# peripherals.net
KiCad netlist of a schematic drawn in Altium Designer
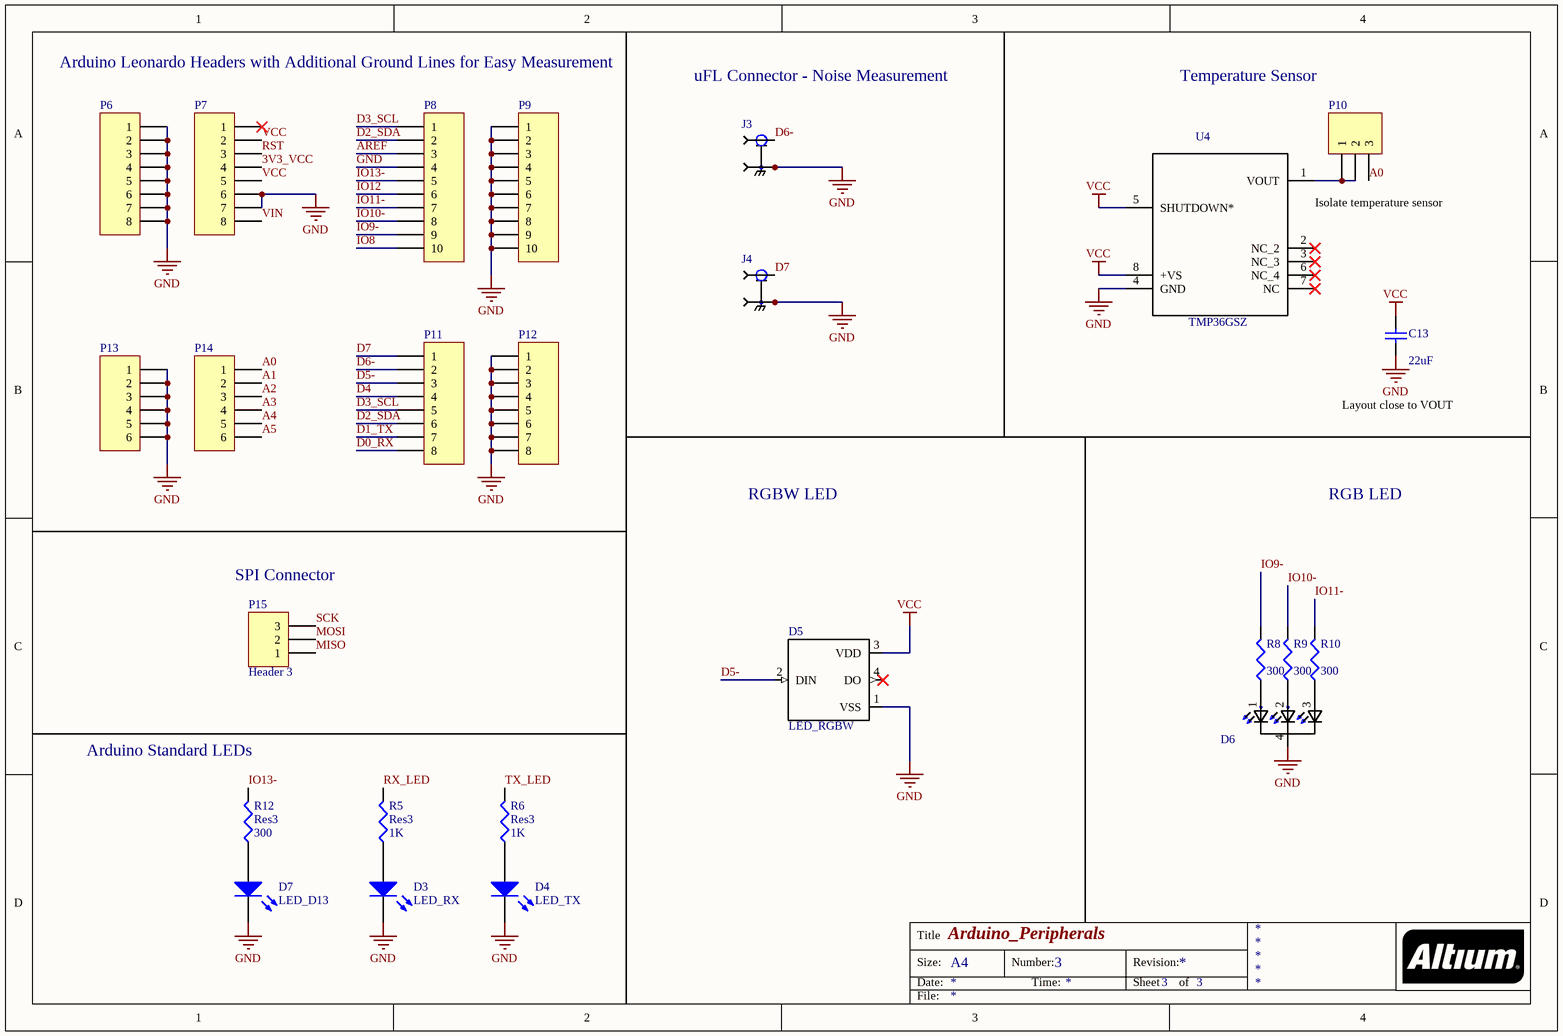
[diagram p0: peripherals.SchDoc]

(export (version "E")
  (design (tool "Eeschema 10.0.6"))
  (components
    (comp (ref "C13")
      (value "22uF")
      (footprint "C1206")
      (description "Capacitor (Semiconductor SIM Model)")
      (fields
        (field (name "DIGIKEYPARTNO") "1276-3300-1-ND")
        (field (name "Comment") "Cap Semi")
        (field (name "PUBLISHER") "Altium Limited")
      )
      (libsource (lib "Miscellaneous Devices") (part "Cap Semi"))
    )
    (comp (ref "D3")
      (value "LED_RX")
      (footprint "3.2X1.6X1.1")
      (description "Typical RED, GREEN, YELLOW, AMBER GaAs LED")
      (fields (field (name "PUBLISHER") "Altium Limited"))
      (libsource (lib "Miscellaneous Devices") (part "LED2"))
    )
    (comp (ref "D4")
      (value "LED_TX")
      (footprint "3.2X1.6X1.1")
      (description "Typical RED, GREEN, YELLOW, AMBER GaAs LED")
      (fields (field (name "PUBLISHER") "Altium Limited"))
      (libsource (lib "Miscellaneous Devices") (part "LED2"))
    )
    (comp (ref "D5")
      (value "LED_RGBW")
      (footprint "*LED_IN-PI554FCH")
      (description "5050RGB with integrated IC built in 4 PIN Â•Viewing angle: 120 degrees")
      (fields (field (name "MP") "IN-PI554FCH") (field (name "MF") "Inolux"))
      (libsource (lib "IN-PI554FCH") (part "IN-PI554FCH"))
    )
    (comp (ref "D6")
      (value "LED_RGB")
      (footprint "*LED_ASMB-KTF0-0A306")
      (description "2220 Tricolor PLCC4 Surface Mount LED")
      (fields (field (name "MP") "XZM2CRKM2DGFBB45SCCB") (field (name "MF") "SunLED"))
      (libsource (lib "ASMB-KTF0-0A306") (part "ASMB-KTF0-0A306"))
    )
    (comp (ref "D7")
      (value "LED_D13")
      (footprint "3.2X1.6X1.1")
      (description "Typical RED, GREEN, YELLOW, AMBER GaAs LED")
      (fields (field (name "PUBLISHER") "Altium Limited"))
      (libsource (lib "Miscellaneous Devices") (part "LED2"))
    )
    (comp (ref "J3")
      (value "U.FL-R-SMT(10)")
      (footprint "*TE_HRS_U.FL-R-SMT(10)")
      (description "U.FL Series 50 Ohm Receptacle Male Pins Ultra Small SMT Coaxial Connector")
      (fields (field (name "MF") "Hirose") (field (name "MP") "U.FL-R-SMT_10_"))
      (libsource (lib "U.FL-R-SMT_10_") (part "U.FL-R-SMT(10)"))
    )
    (comp (ref "J4")
      (value "U.FL-R-SMT(10)")
      (footprint "*TE_HRS_U.FL-R-SMT(10)")
      (description "U.FL Series 50 Ohm Receptacle Male Pins Ultra Small SMT Coaxial Connector")
      (fields (field (name "MF") "Hirose") (field (name "MP") "U.FL-R-SMT_10_"))
      (libsource (lib "U.FL-R-SMT_10_") (part "U.FL-R-SMT(10)"))
    )
    (comp (ref "P6")
      (value "GND")
      (footprint "HDR1X8")
      (description "Header, 8-Pin")
      (fields (field (name "PUBLISHER") "Altium Limited"))
      (libsource (lib "Miscellaneous Connectors") (part "Header 8"))
    )
    (comp (ref "P7")
      (value "P4")
      (footprint "HDR1X8")
      (description "Header, 8-Pin")
      (fields (field (name "PUBLISHER") "Altium Limited"))
      (libsource (lib "Miscellaneous Connectors") (part "Header 8"))
    )
    (comp (ref "P8")
      (value "P1")
      (footprint "HDR1X10")
      (description "Header, 10-Pin")
      (fields (field (name "PUBLISHER") "Altium Limited"))
      (libsource (lib "Miscellaneous Connectors") (part "Header 10"))
    )
    (comp (ref "P9")
      (value "GND")
      (footprint "HDR1X10")
      (description "Header, 10-Pin")
      (fields (field (name "PUBLISHER") "Altium Limited"))
      (libsource (lib "Miscellaneous Connectors") (part "Header 10"))
    )
    (comp (ref "P10")
      (value "NC A0")
      (footprint "HDR1X3")
      (description "Header, 3-Pin")
      (fields (field (name "PUBLISHER") "Altium Limited"))
      (libsource (lib "Miscellaneous Connectors") (part "Header 3"))
    )
    (comp (ref "P11")
      (value "P2")
      (footprint "HDR1X8")
      (description "Header, 8-Pin")
      (fields (field (name "PUBLISHER") "Altium Limited"))
      (libsource (lib "") (part "Header 8_1"))
    )
    (comp (ref "P12")
      (value "GND")
      (footprint "HDR1X8")
      (description "Header, 8-Pin")
      (fields (field (name "PUBLISHER") "Altium Limited"))
      (libsource (lib "") (part "Header 8_1"))
    )
    (comp (ref "P13")
      (value "GND")
      (footprint "HDR1X6")
      (description "Header, 6-Pin")
      (fields (field (name "PUBLISHER") "Altium Limited"))
      (libsource (lib "Miscellaneous Connectors") (part "Header 6"))
    )
    (comp (ref "P14")
      (value "P3")
      (footprint "HDR1X6")
      (description "Header, 6-Pin")
      (fields (field (name "PUBLISHER") "Altium Limited"))
      (libsource (lib "Miscellaneous Connectors") (part "Header 6"))
    )
    (comp (ref "P15")
      (value "Header 3")
      (footprint "HDR1X3")
      (description "Header, 3-Pin")
      (fields (field (name "PUBLISHER") "Altium Limited"))
      (libsource (lib "") (part "Header 3_1"))
    )
    (comp (ref "R5")
      (value "Res3")
      (footprint "C1206")
      (description "Resistor")
      (fields (field (name "ALTIUM_VALUE") "1K") (field (name "PUBLISHER") "Altium Limited"))
      (libsource (lib "Miscellaneous Devices") (part "Res3"))
    )
    (comp (ref "R6")
      (value "Res3")
      (footprint "C1206")
      (description "Resistor")
      (fields (field (name "ALTIUM_VALUE") "1K") (field (name "PUBLISHER") "Altium Limited"))
      (libsource (lib "Miscellaneous Devices") (part "Res3"))
    )
    (comp (ref "R8")
      (value "300")
      (footprint "C1206")
      (description "Resistor")
      (fields (field (name "Comment") "Res3") (field (name "PUBLISHER") "Altium Limited"))
      (libsource (lib "Miscellaneous Devices") (part "Res3"))
    )
    (comp (ref "R9")
      (value "300")
      (footprint "C1206")
      (description "Resistor")
      (fields (field (name "Comment") "Res3") (field (name "PUBLISHER") "Altium Limited"))
      (libsource (lib "Miscellaneous Devices") (part "Res3"))
    )
    (comp (ref "R10")
      (value "300")
      (footprint "C1206")
      (description "Resistor")
      (fields (field (name "Comment") "Res3") (field (name "PUBLISHER") "Altium Limited"))
      (libsource (lib "Miscellaneous Devices") (part "Res3"))
    )
    (comp (ref "R12")
      (value "Res3")
      (footprint "C1206")
      (description "Resistor")
      (fields (field (name "ALTIUM_VALUE") "300") (field (name "PUBLISHER") "Altium Limited"))
      (libsource (lib "Miscellaneous Devices") (part "Res3"))
    )
    (comp (ref "U4")
      (value "TMP36GSZ")
      (footprint "*SOIC127P600X175-8N")
      (description "Temp Sensor Analog_Voltage_ Serial _2-Wire_ 8-Pin SOIC N Tube")
      (fields (field (name "MF") "Analog Devices"))
      (libsource (lib "TMP36GSZ") (part "TMP36GSZ"))
    )
  )
  (nets
    (net (code "1") (name "/3V3_VCC") (class "Default")
      (node (ref "P7") (pin "4") (pinfunction "4_4") (pintype "passive"))
    )
    (net (code "2") (name "/A0") (class "Default")
      (node (ref "P10") (pin "3") (pinfunction "3_3") (pintype "passive"))
      (node (ref "P14") (pin "1") (pinfunction "1_1") (pintype "passive"))
    )
    (net (code "3") (name "/A1") (class "Default")
      (node (ref "P14") (pin "2") (pinfunction "2_2") (pintype "passive"))
    )
    (net (code "4") (name "/A2") (class "Default")
      (node (ref "P14") (pin "3") (pinfunction "3_3") (pintype "passive"))
    )
    (net (code "5") (name "/A3") (class "Default")
      (node (ref "P14") (pin "4") (pinfunction "4_4") (pintype "passive"))
    )
    (net (code "6") (name "/A4") (class "Default")
      (node (ref "P14") (pin "5") (pinfunction "5_5") (pintype "passive"))
    )
    (net (code "7") (name "/A5") (class "Default")
      (node (ref "P14") (pin "6") (pinfunction "6_6") (pintype "passive"))
    )
    (net (code "8") (name "/AREF") (class "Default")
      (node (ref "P8") (pin "3") (pinfunction "3_3") (pintype "passive"))
    )
    (net (code "9") (name "/D0_RX") (class "Default")
      (node (ref "P11") (pin "8") (pinfunction "8_8") (pintype "passive"))
    )
    (net (code "10") (name "/D1_TX") (class "Default")
      (node (ref "P11") (pin "7") (pinfunction "7_7") (pintype "passive"))
    )
    (net (code "11") (name "/D2_SDA") (class "Default")
      (node (ref "P11") (pin "6") (pinfunction "6_6") (pintype "passive"))
      (node (ref "P8") (pin "2") (pinfunction "2_2") (pintype "passive"))
    )
    (net (code "12") (name "/D3_SCL") (class "Default")
      (node (ref "P11") (pin "5") (pinfunction "5_5") (pintype "passive"))
      (node (ref "P8") (pin "1") (pinfunction "1_1") (pintype "passive"))
    )
    (net (code "13") (name "/D4") (class "Default")
      (node (ref "P11") (pin "4") (pinfunction "4_4") (pintype "passive"))
    )
    (net (code "14") (name "/D5-") (class "Default")
      (node (ref "D5") (pin "2") (pinfunction "DIN_2") (pintype "input"))
      (node (ref "P11") (pin "3") (pinfunction "3_3") (pintype "passive"))
    )
    (net (code "15") (name "/D6-") (class "Default")
      (node (ref "J3") (pin "1") (pinfunction "SIG_1") (pintype "passive"))
      (node (ref "P11") (pin "2") (pinfunction "2_2") (pintype "passive"))
    )
    (net (code "16") (name "/D7") (class "Default")
      (node (ref "J4") (pin "1") (pinfunction "SIG_1") (pintype "passive"))
      (node (ref "P11") (pin "1") (pinfunction "1_1") (pintype "passive"))
    )
    (net (code "17") (name "/IO8") (class "Default")
      (node (ref "P8") (pin "10") (pinfunction "10_10") (pintype "passive"))
    )
    (net (code "18") (name "/IO9-") (class "Default")
      (node (ref "P8") (pin "9") (pinfunction "9_9") (pintype "passive"))
      (node (ref "R8") (pin "2") (pinfunction "2_2") (pintype "passive"))
    )
    (net (code "19") (name "/IO10-") (class "Default")
      (node (ref "P8") (pin "8") (pinfunction "8_8") (pintype "passive"))
      (node (ref "R9") (pin "2") (pinfunction "2_2") (pintype "passive"))
    )
    (net (code "20") (name "/IO11-") (class "Default")
      (node (ref "P8") (pin "7") (pinfunction "7_7") (pintype "passive"))
      (node (ref "R10") (pin "2") (pinfunction "2_2") (pintype "passive"))
    )
    (net (code "21") (name "/IO12") (class "Default")
      (node (ref "P8") (pin "6") (pinfunction "6_6") (pintype "passive"))
    )
    (net (code "22") (name "/IO13-") (class "Default")
      (node (ref "P8") (pin "5") (pinfunction "5_5") (pintype "passive"))
      (node (ref "R12") (pin "2") (pinfunction "2_2") (pintype "passive"))
    )
    (net (code "23") (name "/MISO") (class "Default")
      (node (ref "P15") (pin "1") (pinfunction "1_1") (pintype "passive"))
    )
    (net (code "24") (name "/MOSI") (class "Default")
      (node (ref "P15") (pin "2") (pinfunction "2_2") (pintype "passive"))
    )
    (net (code "25") (name "/RST") (class "Default")
      (node (ref "P7") (pin "3") (pinfunction "3_3") (pintype "passive"))
    )
    (net (code "26") (name "/RX_LED") (class "Default")
      (node (ref "R5") (pin "2") (pinfunction "2_2") (pintype "passive"))
    )
    (net (code "27") (name "/SCK") (class "Default")
      (node (ref "P15") (pin "3") (pinfunction "3_3") (pintype "passive"))
    )
    (net (code "28") (name "/TX_LED") (class "Default")
      (node (ref "R6") (pin "2") (pinfunction "2_2") (pintype "passive"))
    )
    (net (code "29") (name "/VIN") (class "Default")
      (node (ref "P7") (pin "8") (pinfunction "8_8") (pintype "passive"))
    )
    (net (code "30") (name "GND") (class "Default")
      (node (ref "C13") (pin "1") (pinfunction "1_1") (pintype "passive"))
      (node (ref "D3") (pin "2") (pinfunction "K_2") (pintype "passive"))
      (node (ref "D4") (pin "2") (pinfunction "K_2") (pintype "passive"))
      (node (ref "D5") (pin "1") (pinfunction "VSS_1") (pintype "power_in"))
      (node (ref "D6") (pin "4") (pinfunction "C_4") (pintype "passive"))
      (node (ref "D7") (pin "2") (pinfunction "K_2") (pintype "passive"))
      (node (ref "J3") (pin "2") (pinfunction "GND_2") (pintype "passive"))
      (node (ref "J3") (pin "3") (pinfunction "GND_3") (pintype "passive"))
      (node (ref "J4") (pin "2") (pinfunction "GND_2") (pintype "passive"))
      (node (ref "J4") (pin "3") (pinfunction "GND_3") (pintype "passive"))
      (node (ref "P12") (pin "1") (pinfunction "1_1") (pintype "passive"))
      (node (ref "P12") (pin "2") (pinfunction "2_2") (pintype "passive"))
      (node (ref "P12") (pin "3") (pinfunction "3_3") (pintype "passive"))
      (node (ref "P12") (pin "4") (pinfunction "4_4") (pintype "passive"))
      (node (ref "P12") (pin "5") (pinfunction "5_5") (pintype "passive"))
      (node (ref "P12") (pin "6") (pinfunction "6_6") (pintype "passive"))
      (node (ref "P12") (pin "7") (pinfunction "7_7") (pintype "passive"))
      (node (ref "P12") (pin "8") (pinfunction "8_8") (pintype "passive"))
      (node (ref "P13") (pin "1") (pinfunction "1_1") (pintype "passive"))
      (node (ref "P13") (pin "2") (pinfunction "2_2") (pintype "passive"))
      (node (ref "P13") (pin "3") (pinfunction "3_3") (pintype "passive"))
      (node (ref "P13") (pin "4") (pinfunction "4_4") (pintype "passive"))
      (node (ref "P13") (pin "5") (pinfunction "5_5") (pintype "passive"))
      (node (ref "P13") (pin "6") (pinfunction "6_6") (pintype "passive"))
      (node (ref "P6") (pin "1") (pinfunction "1_1") (pintype "passive"))
      (node (ref "P6") (pin "2") (pinfunction "2_2") (pintype "passive"))
      (node (ref "P6") (pin "3") (pinfunction "3_3") (pintype "passive"))
      (node (ref "P6") (pin "4") (pinfunction "4_4") (pintype "passive"))
      (node (ref "P6") (pin "5") (pinfunction "5_5") (pintype "passive"))
      (node (ref "P6") (pin "6") (pinfunction "6_6") (pintype "passive"))
      (node (ref "P6") (pin "7") (pinfunction "7_7") (pintype "passive"))
      (node (ref "P6") (pin "8") (pinfunction "8_8") (pintype "passive"))
      (node (ref "P7") (pin "6") (pinfunction "6_6") (pintype "passive"))
      (node (ref "P7") (pin "7") (pinfunction "7_7") (pintype "passive"))
      (node (ref "P8") (pin "4") (pinfunction "4_4") (pintype "passive"))
      (node (ref "P9") (pin "1") (pinfunction "1_1") (pintype "passive"))
      (node (ref "P9") (pin "10") (pinfunction "10_10") (pintype "passive"))
      (node (ref "P9") (pin "2") (pinfunction "2_2") (pintype "passive"))
      (node (ref "P9") (pin "3") (pinfunction "3_3") (pintype "passive"))
      (node (ref "P9") (pin "4") (pinfunction "4_4") (pintype "passive"))
      (node (ref "P9") (pin "5") (pinfunction "5_5") (pintype "passive"))
      (node (ref "P9") (pin "6") (pinfunction "6_6") (pintype "passive"))
      (node (ref "P9") (pin "7") (pinfunction "7_7") (pintype "passive"))
      (node (ref "P9") (pin "8") (pinfunction "8_8") (pintype "passive"))
      (node (ref "P9") (pin "9") (pinfunction "9_9") (pintype "passive"))
      (node (ref "U4") (pin "4") (pinfunction "GND_4") (pintype "passive"))
    )
    (net (code "31") (name "Net-(D3-A)") (class "Default")
      (node (ref "D3") (pin "1") (pinfunction "A_1") (pintype "passive"))
      (node (ref "R5") (pin "1") (pinfunction "1_1") (pintype "passive"))
    )
    (net (code "32") (name "Net-(D4-A)") (class "Default")
      (node (ref "D4") (pin "1") (pinfunction "A_1") (pintype "passive"))
      (node (ref "R6") (pin "1") (pinfunction "1_1") (pintype "passive"))
    )
    (net (code "33") (name "Net-(D6-B)") (class "Default")
      (node (ref "D6") (pin "3") (pinfunction "B_3") (pintype "passive"))
      (node (ref "R10") (pin "1") (pinfunction "1_1") (pintype "passive"))
    )
    (net (code "34") (name "Net-(D6-G)") (class "Default")
      (node (ref "D6") (pin "2") (pinfunction "G_2") (pintype "passive"))
      (node (ref "R9") (pin "1") (pinfunction "1_1") (pintype "passive"))
    )
    (net (code "35") (name "Net-(D6-R)") (class "Default")
      (node (ref "D6") (pin "1") (pinfunction "R_1") (pintype "passive"))
      (node (ref "R8") (pin "1") (pinfunction "1_1") (pintype "passive"))
    )
    (net (code "36") (name "Net-(D7-A)") (class "Default")
      (node (ref "D7") (pin "1") (pinfunction "A_1") (pintype "passive"))
      (node (ref "R12") (pin "1") (pinfunction "1_1") (pintype "passive"))
    )
    (net (code "37") (name "Net-(U4-VOUT)") (class "Default")
      (node (ref "P10") (pin "1") (pinfunction "1_1") (pintype "passive"))
      (node (ref "P10") (pin "2") (pinfunction "2_2") (pintype "passive"))
      (node (ref "U4") (pin "1") (pinfunction "VOUT_1") (pintype "passive"))
    )
    (net (code "38") (name "VCC") (class "Default")
      (node (ref "C13") (pin "2") (pinfunction "2_2") (pintype "passive"))
      (node (ref "D5") (pin "3") (pinfunction "VDD_3") (pintype "power_in"))
      (node (ref "P7") (pin "2") (pinfunction "2_2") (pintype "passive"))
      (node (ref "P7") (pin "5") (pinfunction "5_5") (pintype "passive"))
      (node (ref "U4") (pin "5") (pinfunction "SHUTDOWN*_5") (pintype "passive"))
      (node (ref "U4") (pin "8") (pinfunction "+VS_8") (pintype "power_in"))
    )
    (net (code "39") (name "unconnected-(D5-DO-Pad4)") (class "Default")
      (node (ref "D5") (pin "4") (pinfunction "DO_4") (pintype "output+no_connect"))
    )
    (net (code "40") (name "unconnected-(P7-Pad1)") (class "Default")
      (node (ref "P7") (pin "1") (pinfunction "1_1") (pintype "passive+no_connect"))
    )
    (net (code "41") (name "unconnected-(U4-NC-Pad7)") (class "Default")
      (node (ref "U4") (pin "7") (pinfunction "NC_7") (pintype "passive+no_connect"))
    )
    (net (code "42") (name "unconnected-(U4-NC_2-Pad2)") (class "Default")
      (node (ref "U4") (pin "2") (pinfunction "NC_2_2") (pintype "passive+no_connect"))
    )
    (net (code "43") (name "unconnected-(U4-NC_3-Pad3)") (class "Default")
      (node (ref "U4") (pin "3") (pinfunction "NC_3_3") (pintype "passive+no_connect"))
    )
    (net (code "44") (name "unconnected-(U4-NC_4-Pad6)") (class "Default")
      (node (ref "U4") (pin "6") (pinfunction "NC_4_6") (pintype "passive+no_connect"))
    )
  )
)
